# microSD.net
KiCad netlist of a schematic drawn in Altium Designer
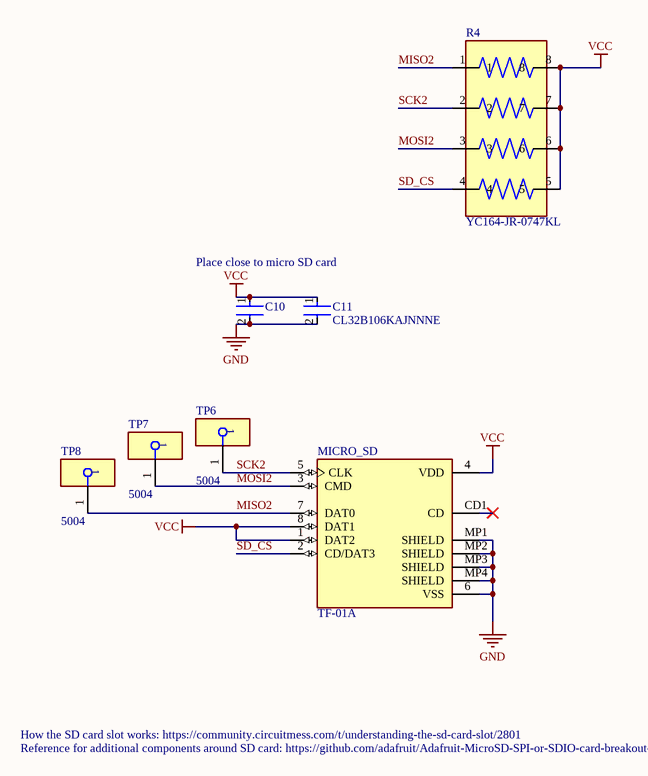
[diagram p0: microSD.SchDoc]

(export (version "E")
  (design (tool "Eeschema 10.0.6"))
  (components
    (comp (ref "C10")
      (value "CC0603KRX7R9BB104")
      (footprint "FP-CC0603-DA-MFG")
      (description "CAP CER 0.1UF 50V X7R 0603")
      (fields (field (name "MANUFACTURER") "YAGEO") (field (name "VOLTAGE") "50 V"))
      (libsource (lib "Altium Content Vault") (part "11868f565c42a9108669ba33697ecf6"))
    )
    (comp (ref "C11")
      (value "CL32B106KAJNNNE")
      (footprint "FP-CL32-IPC_B")
      (description "Cap Ceramic 10uF 25V X7R ±10% SMD 1210 +125°C Embossed T/R")
      (fields (field (name "TOLERANCE") "10%") (field (name "VOLTAGE") "25V"))
      (libsource (lib "Altium Content Vault") (part "b4654b650e69147ec39a6b967a45e02"))
    )
    (comp (ref "MICRO_SD")
      (value "TF-01A")
      (footprint "TF-01A")
      (description "Standard Card Edge Connectors")
      (fields (field (name "MF") "HRO Electronics Co., Ltd.") (field (name "LCSC PART #") "C91145"))
      (libsource (lib "TF-01A") (part "TF-01A"))
    )
    (comp (ref "R4")
      (value "YC164-JR-0747KL")
      (footprint "RESCAXE80P320X160X70-8N")
      (fields (field (name "MF") "Yageo") (field (name "LCSC PART #") "C779384"))
      (libsource (lib "YC164-JR-0747KL") (part "YC164-JR-0747KL"))
    )
    (comp (ref "TP6")
      (value "5004")
      (footprint "FP-5004-MFG")
      (description "PC TEST POINT MINIATURE YELLOW")
      (fields
        (field (name "MANUFACTURER") "Keystone")
        (field (name "OCTOPART") "https://octopart.com/5004-keystone-28591")
      )
      (libsource (lib "Altium Content Vault") (part "98815daf2f2c152b0c43f5ab9800df6"))
    )
    (comp (ref "TP7")
      (value "5004")
      (footprint "FP-5004-MFG")
      (description "PC TEST POINT MINIATURE YELLOW")
      (fields
        (field (name "MANUFACTURER") "Keystone")
        (field (name "OCTOPART") "https://octopart.com/5004-keystone-28591")
      )
      (libsource (lib "Altium Content Vault") (part "98815daf2f2c152b0c43f5ab9800df6"))
    )
    (comp (ref "TP8")
      (value "5004")
      (footprint "FP-5004-MFG")
      (description "PC TEST POINT MINIATURE YELLOW")
      (fields
        (field (name "MANUFACTURER") "Keystone")
        (field (name "OCTOPART") "https://octopart.com/5004-keystone-28591")
      )
      (libsource (lib "Altium Content Vault") (part "98815daf2f2c152b0c43f5ab9800df6"))
    )
  )
  (nets
    (net (code "1") (name "/MISO2") (class "Default")
      (node (ref "MICRO_SD") (pin "7") (pinfunction "DAT0_7") (pintype "bidirectional"))
      (node (ref "R4") (pin "1") (pinfunction "1_1") (pintype "passive"))
      (node (ref "TP8") (pin "1") (pinfunction "1_1") (pintype "passive"))
    )
    (net (code "2") (name "/MOSI2") (class "Default")
      (node (ref "MICRO_SD") (pin "3") (pinfunction "CMD_3") (pintype "bidirectional"))
      (node (ref "R4") (pin "3") (pinfunction "3_3") (pintype "passive"))
      (node (ref "TP7") (pin "1") (pinfunction "1_1") (pintype "passive"))
    )
    (net (code "3") (name "/SCK2") (class "Default")
      (node (ref "MICRO_SD") (pin "5") (pinfunction "CLK_5") (pintype "bidirectional"))
      (node (ref "R4") (pin "2") (pinfunction "2_2") (pintype "passive"))
      (node (ref "TP6") (pin "1") (pinfunction "1_1") (pintype "passive"))
    )
    (net (code "4") (name "/SD_CS") (class "Default")
      (node (ref "MICRO_SD") (pin "2") (pinfunction "CD/DAT3_2") (pintype "bidirectional"))
      (node (ref "R4") (pin "4") (pinfunction "4_4") (pintype "passive"))
    )
    (net (code "5") (name "GND") (class "Default")
      (node (ref "C10") (pin "2") (pinfunction "2_2") (pintype "passive"))
      (node (ref "C11") (pin "2") (pinfunction "2_2") (pintype "passive"))
      (node (ref "MICRO_SD") (pin "6") (pinfunction "VSS_6") (pintype "power_in"))
      (node (ref "MICRO_SD") (pin "MP1") (pinfunction "SHIELD_MP1") (pintype "power_in"))
      (node (ref "MICRO_SD") (pin "MP2") (pinfunction "SHIELD_MP2") (pintype "power_in"))
      (node (ref "MICRO_SD") (pin "MP3") (pinfunction "SHIELD_MP3") (pintype "power_in"))
      (node (ref "MICRO_SD") (pin "MP4") (pinfunction "SHIELD_MP4") (pintype "power_in"))
    )
    (net (code "6") (name "VCC") (class "Default")
      (node (ref "C10") (pin "1") (pinfunction "1_1") (pintype "passive"))
      (node (ref "C11") (pin "1") (pinfunction "1_1") (pintype "passive"))
      (node (ref "MICRO_SD") (pin "1") (pinfunction "DAT2_1") (pintype "bidirectional"))
      (node (ref "MICRO_SD") (pin "4") (pinfunction "VDD_4") (pintype "power_in"))
      (node (ref "MICRO_SD") (pin "8") (pinfunction "DAT1_8") (pintype "bidirectional"))
      (node (ref "R4") (pin "5") (pinfunction "5_5") (pintype "passive"))
      (node (ref "R4") (pin "6") (pinfunction "6_6") (pintype "passive"))
      (node (ref "R4") (pin "7") (pinfunction "7_7") (pintype "passive"))
      (node (ref "R4") (pin "8") (pinfunction "8_8") (pintype "passive"))
    )
    (net (code "7") (name "unconnected-(MICRO_SD-CD-PadCD1)") (class "Default")
      (node (ref "MICRO_SD") (pin "CD1") (pinfunction "CD_CD1") (pintype "passive+no_connect"))
    )
  )
)
